# LevelBridge.net
KiCad netlist of a schematic drawn in Altium Designer
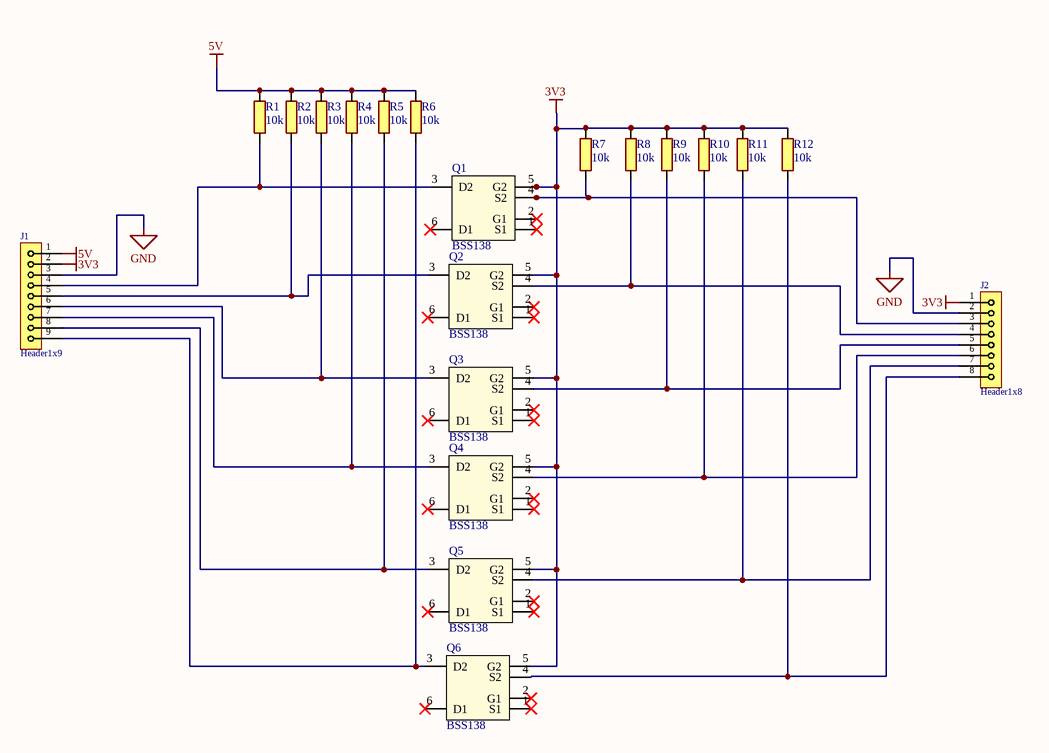
[diagram p0: LevelBridge.SchDoc]

(export (version "E")
  (design (tool "Eeschema 10.0.6"))
  (components
    (comp (ref "J1")
      (value "Header1x9")
      (footprint "HDRV9W64P254_1X9_2286X254X900B")
      (libsource (lib "OVLib") (part "Header1x9"))
    )
    (comp (ref "J2")
      (value "Header1x8")
      (footprint "HDRV8W64P254_1X8_2032X254X900B")
      (libsource (lib "OVLib") (part "Header1x8"))
    )
    (comp (ref "Q1")
      (value "BSS138")
      (footprint "PCBComponent_1")
      (description "FET SM NCH 50V 220mA SOT23-3L")
      (libsource (lib "BSS138") (part "BSS138"))
    )
    (comp (ref "Q2")
      (value "BSS138")
      (footprint "PCBComponent_1")
      (description "FET SM NCH 50V 220mA SOT23-3L")
      (libsource (lib "BSS138") (part "BSS138"))
    )
    (comp (ref "Q3")
      (value "BSS138")
      (footprint "PCBComponent_1")
      (description "FET SM NCH 50V 220mA SOT23-3L")
      (libsource (lib "BSS138") (part "BSS138"))
    )
    (comp (ref "Q4")
      (value "BSS138")
      (footprint "PCBComponent_1")
      (description "FET SM NCH 50V 220mA SOT23-3L")
      (libsource (lib "BSS138") (part "BSS138"))
    )
    (comp (ref "Q5")
      (value "BSS138")
      (footprint "PCBComponent_1")
      (description "FET SM NCH 50V 220mA SOT23-3L")
      (libsource (lib "BSS138") (part "BSS138"))
    )
    (comp (ref "Q6")
      (value "BSS138")
      (footprint "PCBComponent_1")
      (description "FET SM NCH 50V 220mA SOT23-3L")
      (libsource (lib "BSS138") (part "BSS138"))
    )
    (comp (ref "R1")
      (value "10k")
      (footprint "RESC0603(1608)_N")
      (description "0.1W 1% Thick film resistor")
      (libsource (lib "OVLib") (part "Resistor2"))
    )
    (comp (ref "R2")
      (value "10k")
      (footprint "RESC0603(1608)_N")
      (description "0.1W 1% Thick film resistor")
      (libsource (lib "OVLib") (part "Resistor2"))
    )
    (comp (ref "R3")
      (value "10k")
      (footprint "RESC0603(1608)_N")
      (description "0.1W 1% Thick film resistor")
      (libsource (lib "OVLib") (part "Resistor2"))
    )
    (comp (ref "R4")
      (value "10k")
      (footprint "RESC0603(1608)_N")
      (description "0.1W 1% Thick film resistor")
      (libsource (lib "OVLib") (part "Resistor2"))
    )
    (comp (ref "R5")
      (value "10k")
      (footprint "RESC0603(1608)_N")
      (description "0.1W 1% Thick film resistor")
      (libsource (lib "OVLib") (part "Resistor2"))
    )
    (comp (ref "R6")
      (value "10k")
      (footprint "RESC0603(1608)_N")
      (description "0.1W 1% Thick film resistor")
      (libsource (lib "OVLib") (part "Resistor2"))
    )
    (comp (ref "R7")
      (value "10k")
      (footprint "RESC0603(1608)_N")
      (description "0.1W 1% Thick film resistor")
      (libsource (lib "OVLib") (part "Resistor2"))
    )
    (comp (ref "R8")
      (value "10k")
      (footprint "RESC0603(1608)_N")
      (description "0.1W 1% Thick film resistor")
      (libsource (lib "OVLib") (part "Resistor2"))
    )
    (comp (ref "R9")
      (value "10k")
      (footprint "RESC0603(1608)_N")
      (description "0.1W 1% Thick film resistor")
      (libsource (lib "OVLib") (part "Resistor2"))
    )
    (comp (ref "R10")
      (value "10k")
      (footprint "RESC0603(1608)_N")
      (description "0.1W 1% Thick film resistor")
      (libsource (lib "OVLib") (part "Resistor2"))
    )
    (comp (ref "R11")
      (value "10k")
      (footprint "RESC0603(1608)_N")
      (description "0.1W 1% Thick film resistor")
      (libsource (lib "OVLib") (part "Resistor2"))
    )
    (comp (ref "R12")
      (value "10k")
      (footprint "RESC0603(1608)_N")
      (description "0.1W 1% Thick film resistor")
      (libsource (lib "OVLib") (part "Resistor2"))
    )
  )
  (nets
    (net (code "1") (name "3V3") (class "Default")
      (node (ref "J1") (pin "2") (pinfunction "2_2") (pintype "passive"))
      (node (ref "J2") (pin "1") (pinfunction "1_1") (pintype "passive"))
      (node (ref "Q1") (pin "5") (pinfunction "G2_5") (pintype "passive"))
      (node (ref "Q2") (pin "5") (pinfunction "G2_5") (pintype "passive"))
      (node (ref "Q3") (pin "5") (pinfunction "G2_5") (pintype "passive"))
      (node (ref "Q4") (pin "5") (pinfunction "G2_5") (pintype "passive"))
      (node (ref "Q5") (pin "5") (pinfunction "G2_5") (pintype "passive"))
      (node (ref "Q6") (pin "5") (pinfunction "G2_5") (pintype "passive"))
      (node (ref "R10") (pin "2") (pinfunction "2_2") (pintype "passive"))
      (node (ref "R11") (pin "2") (pinfunction "2_2") (pintype "passive"))
      (node (ref "R12") (pin "2") (pinfunction "2_2") (pintype "passive"))
      (node (ref "R7") (pin "2") (pinfunction "2_2") (pintype "passive"))
      (node (ref "R8") (pin "2") (pinfunction "2_2") (pintype "passive"))
      (node (ref "R9") (pin "2") (pinfunction "2_2") (pintype "passive"))
    )
    (net (code "2") (name "5V") (class "Default")
      (node (ref "J1") (pin "1") (pinfunction "1_1") (pintype "passive"))
      (node (ref "R1") (pin "2") (pinfunction "2_2") (pintype "passive"))
      (node (ref "R2") (pin "2") (pinfunction "2_2") (pintype "passive"))
      (node (ref "R3") (pin "2") (pinfunction "2_2") (pintype "passive"))
      (node (ref "R4") (pin "2") (pinfunction "2_2") (pintype "passive"))
      (node (ref "R5") (pin "2") (pinfunction "2_2") (pintype "passive"))
      (node (ref "R6") (pin "2") (pinfunction "2_2") (pintype "passive"))
    )
    (net (code "3") (name "GND") (class "Default")
      (node (ref "J1") (pin "3") (pinfunction "3_3") (pintype "passive"))
      (node (ref "J2") (pin "2") (pinfunction "2_2") (pintype "passive"))
    )
    (net (code "4") (name "Net-(Q1-D2)") (class "Default")
      (node (ref "J1") (pin "4") (pinfunction "4_4") (pintype "passive"))
      (node (ref "Q1") (pin "3") (pinfunction "D2_3") (pintype "passive"))
      (node (ref "R1") (pin "1") (pinfunction "1_1") (pintype "passive"))
    )
    (net (code "5") (name "Net-(Q1-S2)") (class "Default")
      (node (ref "J2") (pin "3") (pinfunction "3_3") (pintype "passive"))
      (node (ref "Q1") (pin "4") (pinfunction "S2_4") (pintype "passive"))
      (node (ref "R7") (pin "1") (pinfunction "1_1") (pintype "passive"))
    )
    (net (code "6") (name "Net-(Q2-D2)") (class "Default")
      (node (ref "J1") (pin "5") (pinfunction "5_5") (pintype "passive"))
      (node (ref "Q2") (pin "3") (pinfunction "D2_3") (pintype "passive"))
      (node (ref "R2") (pin "1") (pinfunction "1_1") (pintype "passive"))
    )
    (net (code "7") (name "Net-(Q2-S2)") (class "Default")
      (node (ref "J2") (pin "4") (pinfunction "4_4") (pintype "passive"))
      (node (ref "Q2") (pin "4") (pinfunction "S2_4") (pintype "passive"))
      (node (ref "R8") (pin "1") (pinfunction "1_1") (pintype "passive"))
    )
    (net (code "8") (name "Net-(Q3-D2)") (class "Default")
      (node (ref "J1") (pin "6") (pinfunction "6_6") (pintype "passive"))
      (node (ref "Q3") (pin "3") (pinfunction "D2_3") (pintype "passive"))
      (node (ref "R3") (pin "1") (pinfunction "1_1") (pintype "passive"))
    )
    (net (code "9") (name "Net-(Q3-S2)") (class "Default")
      (node (ref "J2") (pin "5") (pinfunction "5_5") (pintype "passive"))
      (node (ref "Q3") (pin "4") (pinfunction "S2_4") (pintype "passive"))
      (node (ref "R9") (pin "1") (pinfunction "1_1") (pintype "passive"))
    )
    (net (code "10") (name "Net-(Q4-D2)") (class "Default")
      (node (ref "J1") (pin "7") (pinfunction "7_7") (pintype "passive"))
      (node (ref "Q4") (pin "3") (pinfunction "D2_3") (pintype "passive"))
      (node (ref "R4") (pin "1") (pinfunction "1_1") (pintype "passive"))
    )
    (net (code "11") (name "Net-(Q4-S2)") (class "Default")
      (node (ref "J2") (pin "6") (pinfunction "6_6") (pintype "passive"))
      (node (ref "Q4") (pin "4") (pinfunction "S2_4") (pintype "passive"))
      (node (ref "R10") (pin "1") (pinfunction "1_1") (pintype "passive"))
    )
    (net (code "12") (name "Net-(Q5-D2)") (class "Default")
      (node (ref "J1") (pin "8") (pinfunction "8_8") (pintype "passive"))
      (node (ref "Q5") (pin "3") (pinfunction "D2_3") (pintype "passive"))
      (node (ref "R5") (pin "1") (pinfunction "1_1") (pintype "passive"))
    )
    (net (code "13") (name "Net-(Q5-S2)") (class "Default")
      (node (ref "J2") (pin "7") (pinfunction "7_7") (pintype "passive"))
      (node (ref "Q5") (pin "4") (pinfunction "S2_4") (pintype "passive"))
      (node (ref "R11") (pin "1") (pinfunction "1_1") (pintype "passive"))
    )
    (net (code "14") (name "Net-(Q6-D2)") (class "Default")
      (node (ref "J1") (pin "9") (pinfunction "9_9") (pintype "passive"))
      (node (ref "Q6") (pin "3") (pinfunction "D2_3") (pintype "passive"))
      (node (ref "R6") (pin "1") (pinfunction "1_1") (pintype "passive"))
    )
    (net (code "15") (name "Net-(Q6-S2)") (class "Default")
      (node (ref "J2") (pin "8") (pinfunction "8_8") (pintype "passive"))
      (node (ref "Q6") (pin "4") (pinfunction "S2_4") (pintype "passive"))
      (node (ref "R12") (pin "1") (pinfunction "1_1") (pintype "passive"))
    )
    (net (code "16") (name "unconnected-(Q1-D1-Pad6)") (class "Default")
      (node (ref "Q1") (pin "6") (pinfunction "D1_6") (pintype "passive+no_connect"))
    )
    (net (code "17") (name "unconnected-(Q1-G1-Pad2)") (class "Default")
      (node (ref "Q1") (pin "2") (pinfunction "G1_2") (pintype "passive+no_connect"))
    )
    (net (code "18") (name "unconnected-(Q1-S1-Pad1)") (class "Default")
      (node (ref "Q1") (pin "1") (pinfunction "S1_1") (pintype "passive+no_connect"))
    )
    (net (code "19") (name "unconnected-(Q2-D1-Pad6)") (class "Default")
      (node (ref "Q2") (pin "6") (pinfunction "D1_6") (pintype "passive+no_connect"))
    )
    (net (code "20") (name "unconnected-(Q2-G1-Pad2)") (class "Default")
      (node (ref "Q2") (pin "2") (pinfunction "G1_2") (pintype "passive+no_connect"))
    )
    (net (code "21") (name "unconnected-(Q2-S1-Pad1)") (class "Default")
      (node (ref "Q2") (pin "1") (pinfunction "S1_1") (pintype "passive+no_connect"))
    )
    (net (code "22") (name "unconnected-(Q3-D1-Pad6)") (class "Default")
      (node (ref "Q3") (pin "6") (pinfunction "D1_6") (pintype "passive+no_connect"))
    )
    (net (code "23") (name "unconnected-(Q3-G1-Pad2)") (class "Default")
      (node (ref "Q3") (pin "2") (pinfunction "G1_2") (pintype "passive+no_connect"))
    )
    (net (code "24") (name "unconnected-(Q3-S1-Pad1)") (class "Default")
      (node (ref "Q3") (pin "1") (pinfunction "S1_1") (pintype "passive+no_connect"))
    )
    (net (code "25") (name "unconnected-(Q4-D1-Pad6)") (class "Default")
      (node (ref "Q4") (pin "6") (pinfunction "D1_6") (pintype "passive+no_connect"))
    )
    (net (code "26") (name "unconnected-(Q4-G1-Pad2)") (class "Default")
      (node (ref "Q4") (pin "2") (pinfunction "G1_2") (pintype "passive+no_connect"))
    )
    (net (code "27") (name "unconnected-(Q4-S1-Pad1)") (class "Default")
      (node (ref "Q4") (pin "1") (pinfunction "S1_1") (pintype "passive+no_connect"))
    )
    (net (code "28") (name "unconnected-(Q5-D1-Pad6)") (class "Default")
      (node (ref "Q5") (pin "6") (pinfunction "D1_6") (pintype "passive+no_connect"))
    )
    (net (code "29") (name "unconnected-(Q5-G1-Pad2)") (class "Default")
      (node (ref "Q5") (pin "2") (pinfunction "G1_2") (pintype "passive+no_connect"))
    )
    (net (code "30") (name "unconnected-(Q5-S1-Pad1)") (class "Default")
      (node (ref "Q5") (pin "1") (pinfunction "S1_1") (pintype "passive+no_connect"))
    )
    (net (code "31") (name "unconnected-(Q6-D1-Pad6)") (class "Default")
      (node (ref "Q6") (pin "6") (pinfunction "D1_6") (pintype "passive+no_connect"))
    )
    (net (code "32") (name "unconnected-(Q6-G1-Pad2)") (class "Default")
      (node (ref "Q6") (pin "2") (pinfunction "G1_2") (pintype "passive+no_connect"))
    )
    (net (code "33") (name "unconnected-(Q6-S1-Pad1)") (class "Default")
      (node (ref "Q6") (pin "1") (pinfunction "S1_1") (pintype "passive+no_connect"))
    )
  )
)
